# design.net
KiCad netlist of a schematic drawn in Altium Designer
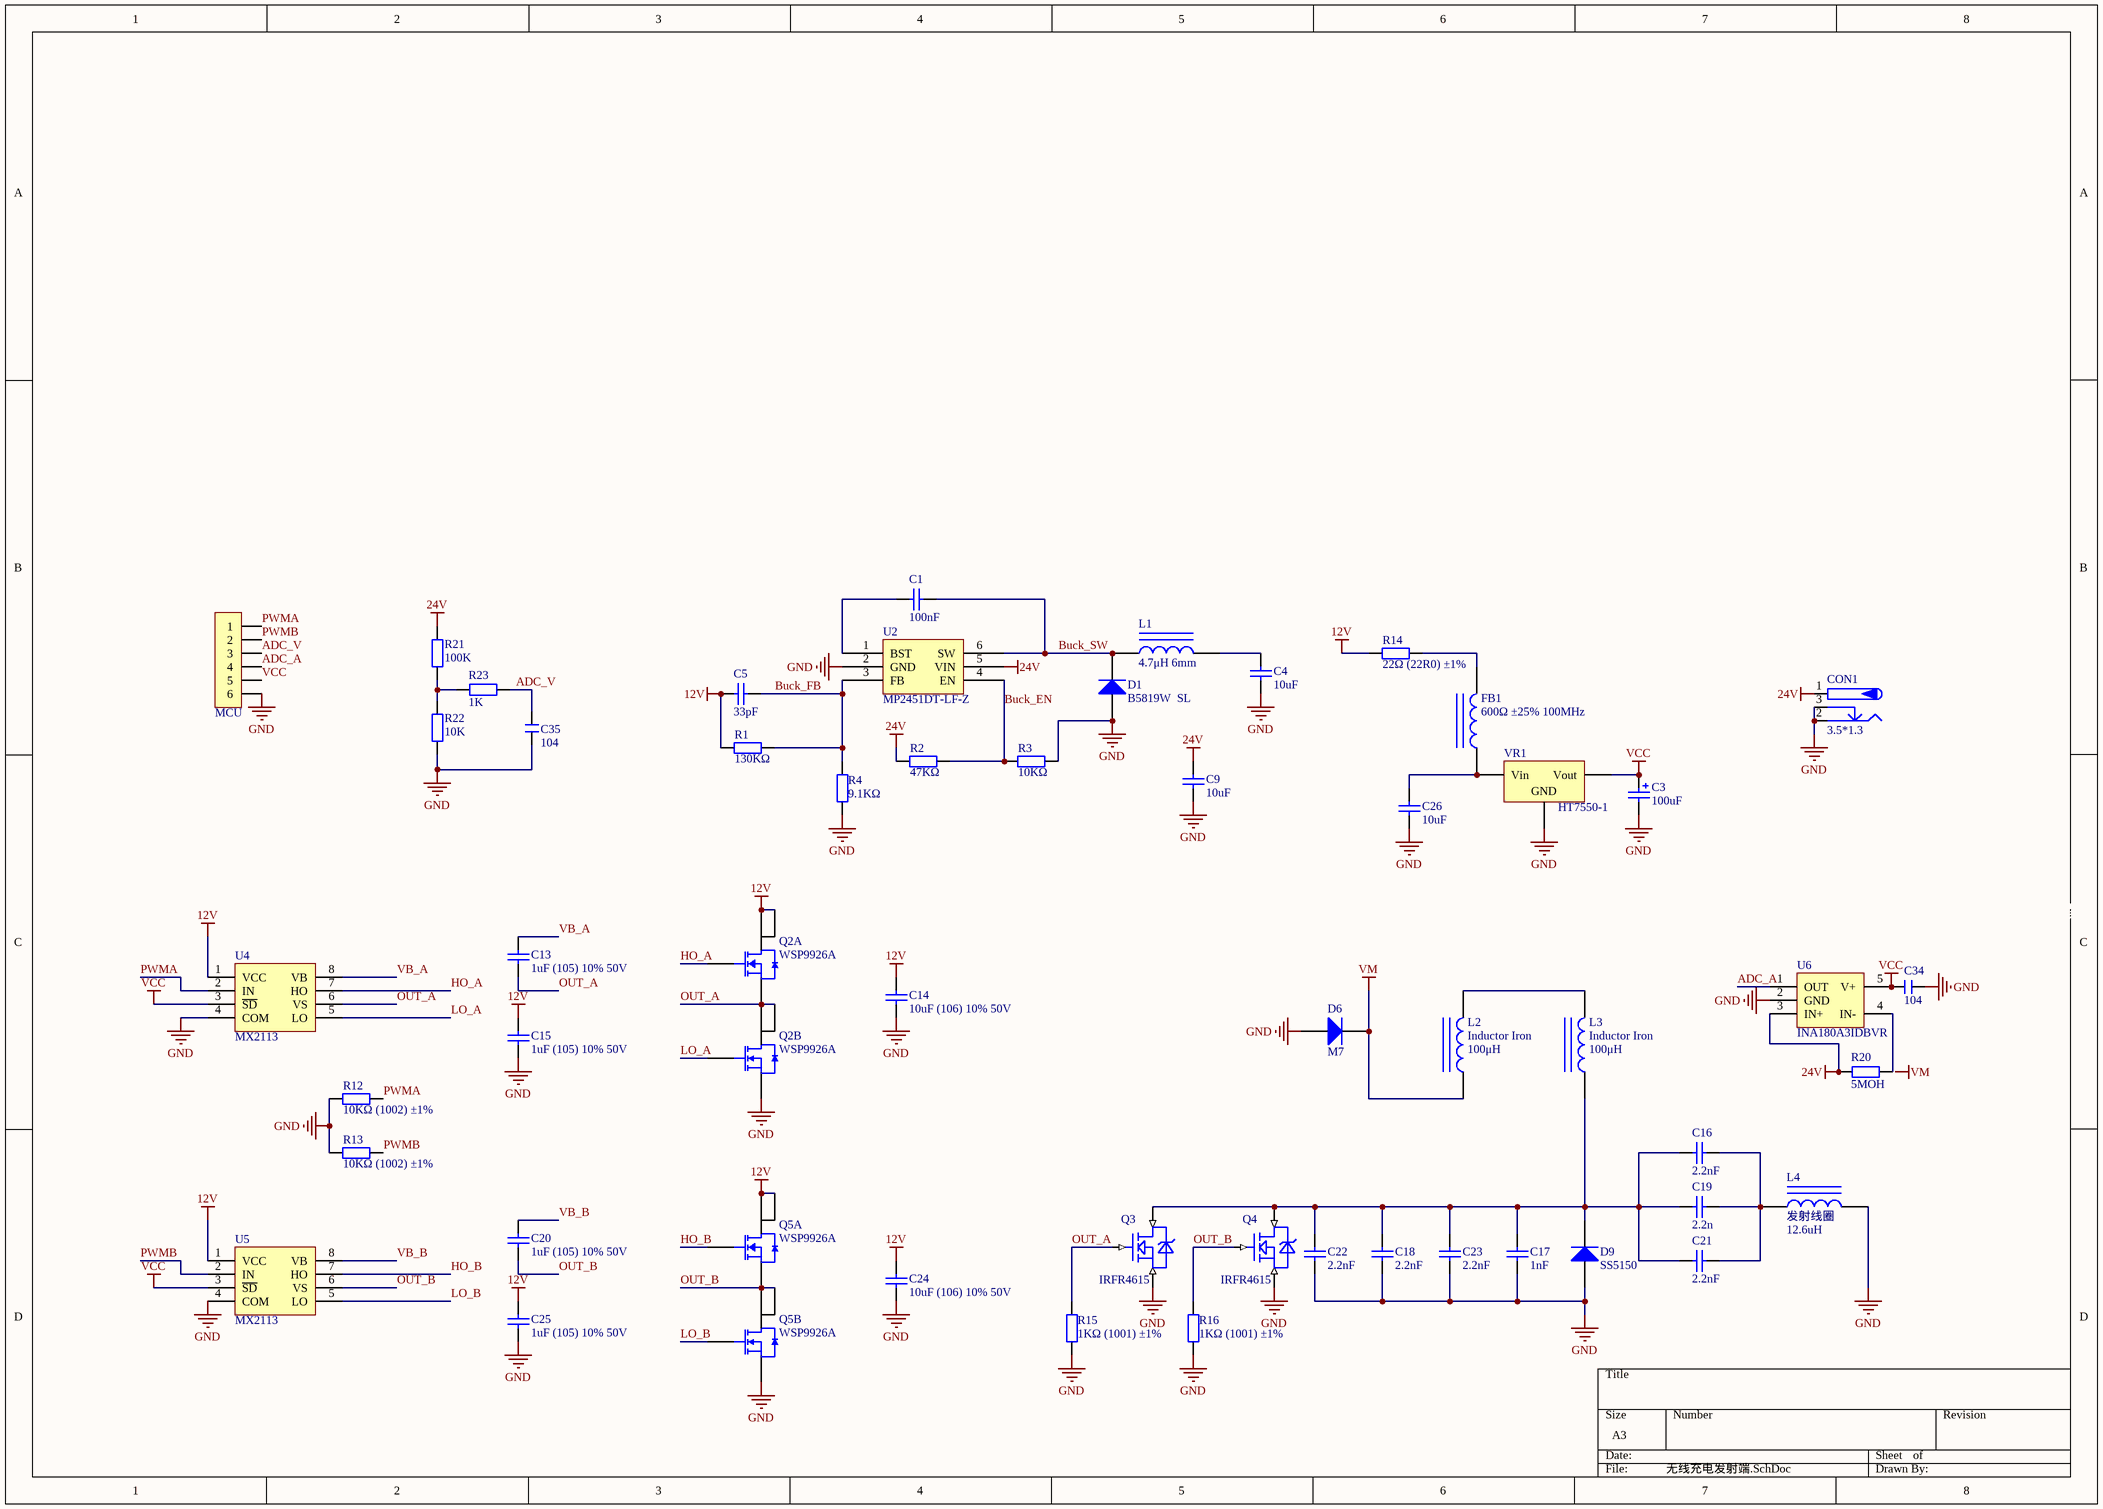
[diagram p0: 无线充电发射端.SchDoc]

(export (version "E")
  (design (tool "Eeschema 10.0.6"))
  (components
    (comp (ref "C1")
      (value "100nF")
      (footprint "0603_C")
      (description "贴片电容")
      (libsource (lib "Miscellaneous Devices LC") (part "0603 100nF (104) 10% 50V"))
    )
    (comp (ref "C3")
      (value "100uF")
      (footprint "CASE-B_3528")
      (description "钽电容")
      (libsource (lib "Miscellaneous Devices LC") (part "3528 100uF (107) 10% 6.3V"))
    )
    (comp (ref "C4")
      (value "10uF")
      (footprint "0805_C")
      (description "贴片电容")
      (libsource (lib "Miscellaneous Devices LC") (part "0805 10uF (106) 10% 25V"))
    )
    (comp (ref "C5")
      (value "33pF")
      (footprint "0603_C")
      (description "贴片电容")
      (libsource (lib "Miscellaneous Devices LC") (part "0603 33pF (330) 5% 50V"))
    )
    (comp (ref "C9")
      (value "10uF")
      (footprint "1206_C")
      (description "贴片电容")
      (libsource (lib "Miscellaneous Devices LC") (part "1206 10uF (106) 10% 50V"))
    )
    (comp (ref "C13")
      (value "1uF (105) 10% 50V")
      (footprint "0805_C")
      (description "贴片电容")
      (libsource (lib "Miscellaneous Devices LC") (part "0805 1uF (105) 10% 50V"))
    )
    (comp (ref "C14")
      (value "10uF (106) 10% 50V")
      (footprint "1206_C")
      (description "贴片电容")
      (libsource (lib "Miscellaneous Devices LC") (part "1206 10uF (106) 10% 50V"))
    )
    (comp (ref "C15")
      (value "1uF (105) 10% 50V")
      (footprint "0805_C")
      (description "贴片电容")
      (libsource (lib "Miscellaneous Devices LC") (part "0805 1uF (105) 10% 50V"))
    )
    (comp (ref "C16")
      (value "2.2nF")
      (footprint "1206_C")
      (description "贴片电容")
      (libsource (lib "Miscellaneous Devices LC") (part "1206 1nF (102) 10% 500V"))
    )
    (comp (ref "C17")
      (value "1nF")
      (footprint "C 1206")
      (description "贴片电容")
      (libsource (lib "Miscellaneous Devices LC") (part "1206 1nF (102) 10% 500V"))
    )
    (comp (ref "C18")
      (value "2.2nF")
      (footprint "C 1206")
      (description "贴片电容")
      (libsource (lib "Miscellaneous Devices LC") (part "1206 1nF (102) 10% 500V"))
    )
    (comp (ref "C19")
      (value "2.2n")
      (footprint "C 1206")
      (description "贴片电容")
      (libsource (lib "Miscellaneous Devices LC") (part "1206 1nF (102) 10% 500V"))
    )
    (comp (ref "C20")
      (value "1uF (105) 10% 50V")
      (footprint "0805_C")
      (description "贴片电容")
      (libsource (lib "Miscellaneous Devices LC") (part "0805 1uF (105) 10% 50V"))
    )
    (comp (ref "C21")
      (value "2.2nF")
      (footprint "C 1206")
      (description "贴片电容")
      (libsource (lib "Miscellaneous Devices LC") (part "1206 1nF (102) 10% 500V"))
    )
    (comp (ref "C22")
      (value "2.2nF")
      (footprint "1206_C")
      (description "贴片电容")
      (libsource (lib "Miscellaneous Devices LC") (part "1206 1nF (102) 10% 500V"))
    )
    (comp (ref "C23")
      (value "2.2nF")
      (footprint "C 1206")
      (description "贴片电容")
      (libsource (lib "Miscellaneous Devices LC") (part "1206 1nF (102) 10% 500V"))
    )
    (comp (ref "C24")
      (value "10uF (106) 10% 50V")
      (footprint "1206_C")
      (description "贴片电容")
      (libsource (lib "Miscellaneous Devices LC") (part "1206 10uF (106) 10% 50V"))
    )
    (comp (ref "C25")
      (value "1uF (105) 10% 50V")
      (footprint "0805_C")
      (description "贴片电容")
      (libsource (lib "Miscellaneous Devices LC") (part "0805 1uF (105) 10% 50V"))
    )
    (comp (ref "C26")
      (value "10uF")
      (footprint "0805_C")
      (description "贴片电容")
      (libsource (lib "Miscellaneous Devices LC") (part "0805 10uF (106) 10% 25V"))
    )
    (comp (ref "C34")
      (value "104")
      (footprint "C 0402")
      (description "无极性贴片电容")
      (fields (field (name "版权归属") "源创客"))
      (libsource (lib "电阻-电容-电感") (part "C"))
    )
    (comp (ref "C35")
      (value "104")
      (footprint "C 0402")
      (description "无极性贴片电容")
      (fields (field (name "版权归属") "源创客"))
      (libsource (lib "电阻-电容-电感") (part "C"))
    )
    (comp (ref "CON1")
      (value "3.5*1.3")
      (footprint "DC-005")
      (description "低压电源接口")
      (fields (field (name "版权归属") "源创客"))
      (libsource (lib "接口类") (part "P-DC"))
    )
    (comp (ref "D1")
      (value "B5819W  SL")
      (footprint "SOD-123")
      (description "肖特基二极管")
      (libsource (lib "Miscellaneous Devices LC") (part "SOD-123 B5819W  SL"))
    )
    (comp (ref "D6")
      (value "M7")
      (footprint "SMA(DO-214AC)_S1")
      (description "二极管")
      (libsource (lib "Miscellaneous Devices LC") (part "SMA(DO-214AC) M7"))
    )
    (comp (ref "D9")
      (value "SS5150")
      (footprint "SMC")
      (description "二极管")
      (libsource (lib "Miscellaneous Devices LC") (part "SMC(DO-214AB) SS36-E3/57T"))
    )
    (comp (ref "FB1")
      (value "600Ω ±25% 100MHz")
      (footprint "0805_L")
      (description "贴片磁珠")
      (libsource (lib "Miscellaneous Devices LC") (part "0805 600Ω 25% 100MHz"))
    )
    (comp (ref "L1")
      (value "4.7μH 6mm")
      (footprint "L6*6")
      (description "Magnetic-Core Inductor")
      (fields (field (name "Comment") "磁屏蔽电感") (field (name "PUBLISHER") "Altium Limited"))
      (libsource (lib "Miscellaneous Devices") (part "Inductor Iron"))
    )
    (comp (ref "L2")
      (value "Inductor Iron")
      (footprint "WHC1250")
      (description "Magnetic-Core Inductor")
      (fields (field (name "ALTIUM_VALUE") "100μH") (field (name "PUBLISHER") "TDK"))
      (libsource (lib "Miscellaneous Devices") (part "Inductor Iron"))
    )
    (comp (ref "L3")
      (value "Inductor Iron")
      (footprint "WHC1250")
      (description "Magnetic-Core Inductor")
      (fields (field (name "ALTIUM_VALUE") "100μH") (field (name "PUBLISHER") "TDK"))
      (libsource (lib "Miscellaneous Devices") (part "Inductor Iron"))
    )
    (comp (ref "L4")
      (value "发射线圈")
      (footprint "IND5X4")
      (description "Magnetic-Core Inductor")
      (fields (field (name "ALTIUM_VALUE") "12.6uH") (field (name "PUBLISHER") "Altium Limited"))
      (libsource (lib "Miscellaneous Devices") (part "Inductor Iron"))
    )
    (comp (ref "MCU")
      (value "HDR-1X6")
      (footprint "HDR-1X6")
      (description "6P接插件")
      (fields (field (name "版权归属") "源创客"))
      (libsource (lib "接插件") (part "Header 6"))
    )
    (comp (ref "Q2")
      (value "WSP9926A")
      (footprint "SOP-8_150mil")
      (description "MOS(场效应管)")
      (libsource (lib "MOS") (part "WSP9926B"))
    )
    (comp (ref "Q3") (value "IRFR4615") (footprint "TO-252") (libsource (lib "*") (part "IRF540")))
    (comp (ref "Q4") (value "IRFR4615") (footprint "TO-252") (libsource (lib "*") (part "IRF540")))
    (comp (ref "Q5")
      (value "WSP9926A")
      (footprint "SOP-8_150mil")
      (description "MOS(场效应管)")
      (libsource (lib "MOS") (part "WSP9926B"))
    )
    (comp (ref "R1")
      (value "130KΩ")
      (footprint "0603_R")
      (description "贴片电阻")
      (libsource (lib "Miscellaneous Devices LC") (part "0603 130KΩ (1303) 1%"))
    )
    (comp (ref "R2")
      (value "47KΩ")
      (footprint "0603_R")
      (description "贴片电阻")
      (libsource (lib "Miscellaneous Devices LC") (part "0603 47KΩ (4702) 1%"))
    )
    (comp (ref "R3")
      (value "10KΩ")
      (footprint "0603_R")
      (description "贴片电阻")
      (libsource (lib "Miscellaneous Devices LC") (part "0603 10KΩ (1002) 1%"))
    )
    (comp (ref "R4")
      (value "9.1KΩ")
      (footprint "0603_R")
      (description "贴片电阻")
      (libsource (lib "Miscellaneous Devices LC") (part "0603 9.1KΩ (9101) 1%"))
    )
    (comp (ref "R12")
      (value "10KΩ (1002) ±1%")
      (footprint "0603_R")
      (description "贴片电阻")
      (libsource (lib "Miscellaneous Devices LC") (part "0603 10KΩ (1002) 1%"))
    )
    (comp (ref "R13")
      (value "10KΩ (1002) ±1%")
      (footprint "0603_R")
      (description "贴片电阻")
      (libsource (lib "Miscellaneous Devices LC") (part "0603 10KΩ (1002) 1%"))
    )
    (comp (ref "R14")
      (value "22Ω (22R0) ±1%")
      (footprint "1206_R")
      (description "贴片电阻")
      (libsource (lib "Miscellaneous Devices LC") (part "1206 22Ω (22R0) 1%"))
    )
    (comp (ref "R15")
      (value "1KΩ (1001) ±1%")
      (footprint "0603_R")
      (description "贴片电阻")
      (libsource (lib "Miscellaneous Devices LC") (part "0603 1KΩ (1001) 1%"))
    )
    (comp (ref "R16")
      (value "1KΩ (1001) ±1%")
      (footprint "0603_R")
      (description "贴片电阻")
      (libsource (lib "Miscellaneous Devices LC") (part "0603 1KΩ (1001) 1%"))
    )
    (comp (ref "R20")
      (value "5MOH")
      (footprint "R 1206")
      (description "贴片电阻")
      (fields (field (name "版权归属") "源创客"))
      (libsource (lib "电阻-电容-电感") (part "R"))
    )
    (comp (ref "R21")
      (value "100K")
      (footprint "R 0402")
      (description "贴片电阻")
      (fields (field (name "版权归属") "源创客"))
      (libsource (lib "电阻-电容-电感") (part "R"))
    )
    (comp (ref "R22")
      (value "10K")
      (footprint "R 0402")
      (description "贴片电阻")
      (fields (field (name "版权归属") "源创客"))
      (libsource (lib "电阻-电容-电感") (part "R"))
    )
    (comp (ref "R23")
      (value "1K")
      (footprint "R 0402")
      (description "贴片电阻")
      (fields (field (name "版权归属") "源创客"))
      (libsource (lib "电阻-电容-电感") (part "R"))
    )
    (comp (ref "U2")
      (value "MP2451DT-LF-Z")
      (footprint "SOT-23-6")
      (description "DC-DC芯片")
      (libsource (lib "Miscellaneous Devices LC") (part "MP2451DT-LF-Z_[C14123]"))
    )
    (comp (ref "U4") (value "MX2113") (footprint "SOP8") (libsource (lib "*") (part "IR2104")))
    (comp (ref "U5") (value "MX2113") (footprint "SOP8") (libsource (lib "*") (part "IR2104")))
    (comp (ref "U6")
      (value "INA180A3IDBVR")
      (footprint "INA180A3IDBVR")
      (description "sot23-5")
      (libsource (lib "Power") (part "INA180A3IDBVR"))
    )
    (comp (ref "VR1")
      (value "HT7550-1")
      (footprint "SOT-89(SOT-89-3)")
      (description "低压差线性稳压(LDO)")
      (libsource (lib "Miscellaneous Devices LC") (part "SOT-89 HT7550-1"))
    )
  )
  (nets
    (net (code "1") (name "/ADC_A") (class "Default")
      (node (ref "MCU") (pin "4") (pinfunction "4_4") (pintype "passive"))
      (node (ref "U6") (pin "1") (pinfunction "OUT_1") (pintype "passive"))
    )
    (net (code "2") (name "/ADC_V") (class "Default")
      (node (ref "C35") (pin "2") (pinfunction "2_2") (pintype "passive"))
      (node (ref "MCU") (pin "3") (pinfunction "3_3") (pintype "passive"))
      (node (ref "R23") (pin "1") (pinfunction "1_1") (pintype "passive"))
    )
    (net (code "3") (name "/Buck_EN") (class "Default")
      (node (ref "R2") (pin "2") (pinfunction "2_2") (pintype "passive"))
      (node (ref "R3") (pin "1") (pinfunction "1_1") (pintype "passive"))
      (node (ref "U2") (pin "4") (pinfunction "EN_4") (pintype "passive"))
    )
    (net (code "4") (name "/Buck_FB") (class "Default")
      (node (ref "C5") (pin "2") (pinfunction "2_2") (pintype "passive"))
      (node (ref "R1") (pin "2") (pinfunction "2_2") (pintype "passive"))
      (node (ref "R4") (pin "2") (pinfunction "2_2") (pintype "passive"))
      (node (ref "U2") (pin "3") (pinfunction "FB_3") (pintype "passive"))
    )
    (net (code "5") (name "/Buck_SW") (class "Default")
      (node (ref "C1") (pin "2") (pinfunction "2_2") (pintype "passive"))
      (node (ref "D1") (pin "2") (pinfunction "K_2") (pintype "passive"))
      (node (ref "L1") (pin "1") (pinfunction "1_1") (pintype "passive"))
      (node (ref "U2") (pin "6") (pinfunction "SW_6") (pintype "passive"))
    )
    (net (code "6") (name "/HO_A") (class "Default")
      (node (ref "Q2") (pin "2") (pinfunction "G_2") (pintype "passive"))
      (node (ref "U4") (pin "7") (pinfunction "HO_7") (pintype "passive"))
    )
    (net (code "7") (name "/HO_B") (class "Default")
      (node (ref "Q5") (pin "2") (pinfunction "G_2") (pintype "passive"))
      (node (ref "U5") (pin "7") (pinfunction "HO_7") (pintype "passive"))
    )
    (net (code "8") (name "/LO_A") (class "Default")
      (node (ref "Q2") (pin "4") (pinfunction "G_4") (pintype "passive"))
      (node (ref "U4") (pin "5") (pinfunction "LO_5") (pintype "passive"))
    )
    (net (code "9") (name "/LO_B") (class "Default")
      (node (ref "Q5") (pin "4") (pinfunction "G_4") (pintype "passive"))
      (node (ref "U5") (pin "5") (pinfunction "LO_5") (pintype "passive"))
    )
    (net (code "10") (name "/OUT_A") (class "Default")
      (node (ref "C13") (pin "1") (pinfunction "1_1") (pintype "passive"))
      (node (ref "Q2") (pin "1") (pinfunction "S_1") (pintype "passive"))
      (node (ref "Q2") (pin "5") (pinfunction "D_5") (pintype "passive"))
      (node (ref "Q2") (pin "6") (pinfunction "D_6") (pintype "passive"))
      (node (ref "Q3") (pin "1") (pinfunction "G_1") (pintype "input"))
      (node (ref "R15") (pin "2") (pinfunction "2_2") (pintype "passive"))
      (node (ref "U4") (pin "6") (pinfunction "VS_6") (pintype "passive"))
    )
    (net (code "11") (name "/OUT_B") (class "Default")
      (node (ref "C20") (pin "1") (pinfunction "1_1") (pintype "passive"))
      (node (ref "Q4") (pin "1") (pinfunction "G_1") (pintype "input"))
      (node (ref "Q5") (pin "1") (pinfunction "S_1") (pintype "passive"))
      (node (ref "Q5") (pin "5") (pinfunction "D_5") (pintype "passive"))
      (node (ref "Q5") (pin "6") (pinfunction "D_6") (pintype "passive"))
      (node (ref "R16") (pin "2") (pinfunction "2_2") (pintype "passive"))
      (node (ref "U5") (pin "6") (pinfunction "VS_6") (pintype "passive"))
    )
    (net (code "12") (name "/PWMA") (class "Default")
      (node (ref "MCU") (pin "1") (pinfunction "1_1") (pintype "passive"))
      (node (ref "R12") (pin "2") (pinfunction "2_2") (pintype "passive"))
      (node (ref "U4") (pin "2") (pinfunction "IN_2") (pintype "passive"))
    )
    (net (code "13") (name "/PWMB") (class "Default")
      (node (ref "MCU") (pin "2") (pinfunction "2_2") (pintype "passive"))
      (node (ref "R13") (pin "2") (pinfunction "2_2") (pintype "passive"))
      (node (ref "U5") (pin "2") (pinfunction "IN_2") (pintype "passive"))
    )
    (net (code "14") (name "/VB_A") (class "Default")
      (node (ref "C13") (pin "2") (pinfunction "2_2") (pintype "passive"))
      (node (ref "U4") (pin "8") (pinfunction "VB_8") (pintype "passive"))
    )
    (net (code "15") (name "/VB_B") (class "Default")
      (node (ref "C20") (pin "2") (pinfunction "2_2") (pintype "passive"))
      (node (ref "U5") (pin "8") (pinfunction "VB_8") (pintype "passive"))
    )
    (net (code "16") (name "12V") (class "Default")
      (node (ref "C14") (pin "2") (pinfunction "2_2") (pintype "passive"))
      (node (ref "C15") (pin "2") (pinfunction "2_2") (pintype "passive"))
      (node (ref "C24") (pin "2") (pinfunction "2_2") (pintype "passive"))
      (node (ref "C25") (pin "2") (pinfunction "2_2") (pintype "passive"))
      (node (ref "C5") (pin "1") (pinfunction "1_1") (pintype "passive"))
      (node (ref "Q2") (pin "7") (pinfunction "D_7") (pintype "passive"))
      (node (ref "Q2") (pin "8") (pinfunction "D_8") (pintype "passive"))
      (node (ref "Q5") (pin "7") (pinfunction "D_7") (pintype "passive"))
      (node (ref "Q5") (pin "8") (pinfunction "D_8") (pintype "passive"))
      (node (ref "R1") (pin "1") (pinfunction "1_1") (pintype "passive"))
      (node (ref "R14") (pin "1") (pinfunction "1_1") (pintype "passive"))
      (node (ref "U4") (pin "1") (pinfunction "VCC_1") (pintype "passive"))
      (node (ref "U5") (pin "1") (pinfunction "VCC_1") (pintype "passive"))
    )
    (net (code "17") (name "24V") (class "Default")
      (node (ref "C9") (pin "2") (pinfunction "2_2") (pintype "passive"))
      (node (ref "CON1") (pin "1") (pintype "power_in"))
      (node (ref "R2") (pin "1") (pinfunction "1_1") (pintype "passive"))
      (node (ref "R20") (pin "1") (pinfunction "1_1") (pintype "passive"))
      (node (ref "R21") (pin "2") (pinfunction "2_2") (pintype "passive"))
      (node (ref "U2") (pin "5") (pinfunction "VIN_5") (pintype "passive"))
      (node (ref "U6") (pin "3") (pinfunction "IN+_3") (pintype "passive"))
    )
    (net (code "18") (name "GND") (class "Default")
      (node (ref "C14") (pin "1") (pinfunction "1_1") (pintype "passive"))
      (node (ref "C15") (pin "1") (pinfunction "1_1") (pintype "passive"))
      (node (ref "C17") (pin "1") (pinfunction "1_1") (pintype "passive"))
      (node (ref "C18") (pin "1") (pinfunction "1_1") (pintype "passive"))
      (node (ref "C22") (pin "1") (pinfunction "1_1") (pintype "passive"))
      (node (ref "C23") (pin "2") (pinfunction "2_2") (pintype "passive"))
      (node (ref "C24") (pin "1") (pinfunction "1_1") (pintype "passive"))
      (node (ref "C25") (pin "1") (pinfunction "1_1") (pintype "passive"))
      (node (ref "C26") (pin "1") (pinfunction "1_1") (pintype "passive"))
      (node (ref "C3") (pin "2") (pinfunction "2_2") (pintype "passive"))
      (node (ref "C34") (pin "1") (pinfunction "1_1") (pintype "passive"))
      (node (ref "C35") (pin "1") (pinfunction "1_1") (pintype "passive"))
      (node (ref "C4") (pin "1") (pinfunction "1_1") (pintype "passive"))
      (node (ref "C9") (pin "1") (pinfunction "1_1") (pintype "passive"))
      (node (ref "CON1") (pin "2") (pintype "power_in"))
      (node (ref "CON1") (pin "3") (pintype "power_in"))
      (node (ref "D1") (pin "1") (pinfunction "A_1") (pintype "passive"))
      (node (ref "D6") (pin "1") (pinfunction "A_1") (pintype "passive"))
      (node (ref "D9") (pin "1") (pinfunction "A_1") (pintype "passive"))
      (node (ref "L4") (pin "2") (pinfunction "2_2") (pintype "passive"))
      (node (ref "MCU") (pin "6") (pinfunction "6_6") (pintype "passive"))
      (node (ref "Q2") (pin "3") (pinfunction "S_3") (pintype "passive"))
      (node (ref "Q3") (pin "3") (pinfunction "S_3") (pintype "input"))
      (node (ref "Q4") (pin "3") (pinfunction "S_3") (pintype "input"))
      (node (ref "Q5") (pin "3") (pinfunction "S_3") (pintype "passive"))
      (node (ref "R12") (pin "1") (pinfunction "1_1") (pintype "passive"))
      (node (ref "R13") (pin "1") (pinfunction "1_1") (pintype "passive"))
      (node (ref "R15") (pin "1") (pinfunction "1_1") (pintype "passive"))
      (node (ref "R16") (pin "1") (pinfunction "1_1") (pintype "passive"))
      (node (ref "R22") (pin "1") (pinfunction "1_1") (pintype "passive"))
      (node (ref "R3") (pin "2") (pinfunction "2_2") (pintype "passive"))
      (node (ref "R4") (pin "1") (pinfunction "1_1") (pintype "passive"))
      (node (ref "U2") (pin "2") (pinfunction "GND_2") (pintype "passive"))
      (node (ref "U4") (pin "4") (pinfunction "COM_4") (pintype "passive"))
      (node (ref "U5") (pin "4") (pinfunction "COM_4") (pintype "passive"))
      (node (ref "U6") (pin "2") (pinfunction "GND_2") (pintype "passive"))
      (node (ref "VR1") (pin "1") (pinfunction "GND_1") (pintype "passive"))
    )
    (net (code "19") (name "Net-(C4-Pad2)") (class "Default")
      (node (ref "C4") (pin "2") (pinfunction "2_2") (pintype "passive"))
      (node (ref "L1") (pin "2") (pinfunction "2_2") (pintype "passive"))
    )
    (net (code "20") (name "Net-(C16-Pad1)") (class "Default")
      (node (ref "C16") (pin "1") (pinfunction "1_1") (pintype "passive"))
      (node (ref "C19") (pin "1") (pinfunction "1_1") (pintype "passive"))
      (node (ref "C21") (pin "1") (pinfunction "1_1") (pintype "passive"))
      (node (ref "L4") (pin "1") (pinfunction "1_1") (pintype "passive"))
    )
    (net (code "21") (name "Net-(D9-K)") (class "Default")
      (node (ref "C16") (pin "2") (pinfunction "2_2") (pintype "passive"))
      (node (ref "C17") (pin "2") (pinfunction "2_2") (pintype "passive"))
      (node (ref "C18") (pin "2") (pinfunction "2_2") (pintype "passive"))
      (node (ref "C19") (pin "2") (pinfunction "2_2") (pintype "passive"))
      (node (ref "C21") (pin "2") (pinfunction "2_2") (pintype "passive"))
      (node (ref "C22") (pin "2") (pinfunction "2_2") (pintype "passive"))
      (node (ref "C23") (pin "1") (pinfunction "1_1") (pintype "passive"))
      (node (ref "D9") (pin "2") (pinfunction "K_2") (pintype "passive"))
      (node (ref "L3") (pin "1") (pinfunction "1_1") (pintype "passive"))
      (node (ref "Q3") (pin "2") (pinfunction "D_2") (pintype "input"))
      (node (ref "Q4") (pin "2") (pinfunction "D_2") (pintype "input"))
    )
    (net (code "22") (name "Net-(FB1-Pad2)") (class "Default")
      (node (ref "FB1") (pin "2") (pinfunction "2_2") (pintype "passive"))
      (node (ref "R14") (pin "2") (pinfunction "2_2") (pintype "passive"))
    )
    (net (code "23") (name "Net-(L2-Pad2)") (class "Default")
      (node (ref "L2") (pin "2") (pinfunction "2_2") (pintype "passive"))
      (node (ref "L3") (pin "2") (pinfunction "2_2") (pintype "passive"))
    )
    (net (code "24") (name "Net-(R21-Pad1)") (class "Default")
      (node (ref "R21") (pin "1") (pinfunction "1_1") (pintype "passive"))
      (node (ref "R22") (pin "2") (pinfunction "2_2") (pintype "passive"))
      (node (ref "R23") (pin "2") (pinfunction "2_2") (pintype "passive"))
    )
    (net (code "25") (name "Net-(U2-BST)") (class "Default")
      (node (ref "C1") (pin "1") (pinfunction "1_1") (pintype "passive"))
      (node (ref "U2") (pin "1") (pinfunction "BST_1") (pintype "passive"))
    )
    (net (code "26") (name "Net-(U6-IN-)") (class "Default")
      (node (ref "R20") (pin "2") (pinfunction "2_2") (pintype "passive"))
      (node (ref "U6") (pin "4") (pinfunction "IN-_4") (pintype "passive"))
    )
    (net (code "27") (name "Net-(VR1-Vin)") (class "Default")
      (node (ref "C26") (pin "2") (pinfunction "2_2") (pintype "passive"))
      (node (ref "FB1") (pin "1") (pinfunction "1_1") (pintype "passive"))
      (node (ref "VR1") (pin "2") (pinfunction "Vin_2") (pintype "passive"))
    )
    (net (code "28") (name "VCC") (class "Default")
      (node (ref "C3") (pin "1") (pinfunction "1_1") (pintype "passive"))
      (node (ref "C34") (pin "2") (pinfunction "2_2") (pintype "passive"))
      (node (ref "MCU") (pin "5") (pinfunction "5_5") (pintype "passive"))
      (node (ref "U4") (pin "3") (pinfunction "~{SD}_3") (pintype "passive"))
      (node (ref "U5") (pin "3") (pinfunction "~{SD}_3") (pintype "passive"))
      (node (ref "U6") (pin "5") (pinfunction "V+_5") (pintype "passive"))
      (node (ref "VR1") (pin "3") (pinfunction "Vout_3") (pintype "passive"))
    )
    (net (code "29") (name "VM") (class "Default")
      (node (ref "D6") (pin "2") (pinfunction "K_2") (pintype "passive"))
      (node (ref "L2") (pin "1") (pinfunction "1_1") (pintype "passive"))
    )
  )
)
